# Mergen_Telemetri_Ate_leme.net
KiCad netlist of a schematic drawn in EAGLE
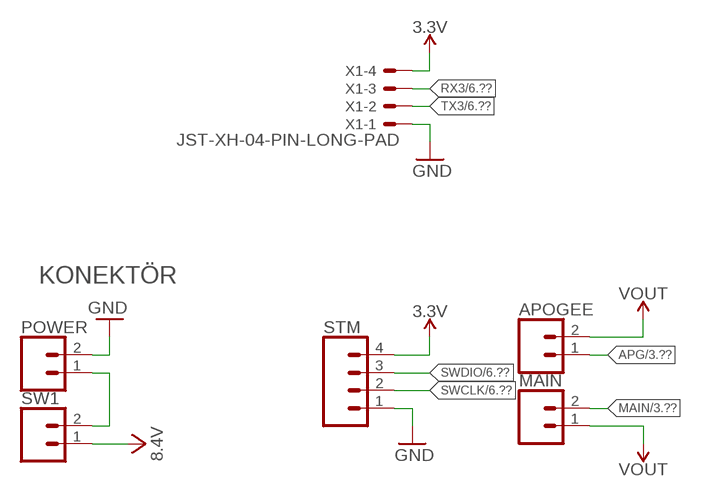
[diagram p0: schematic, sheet 1]
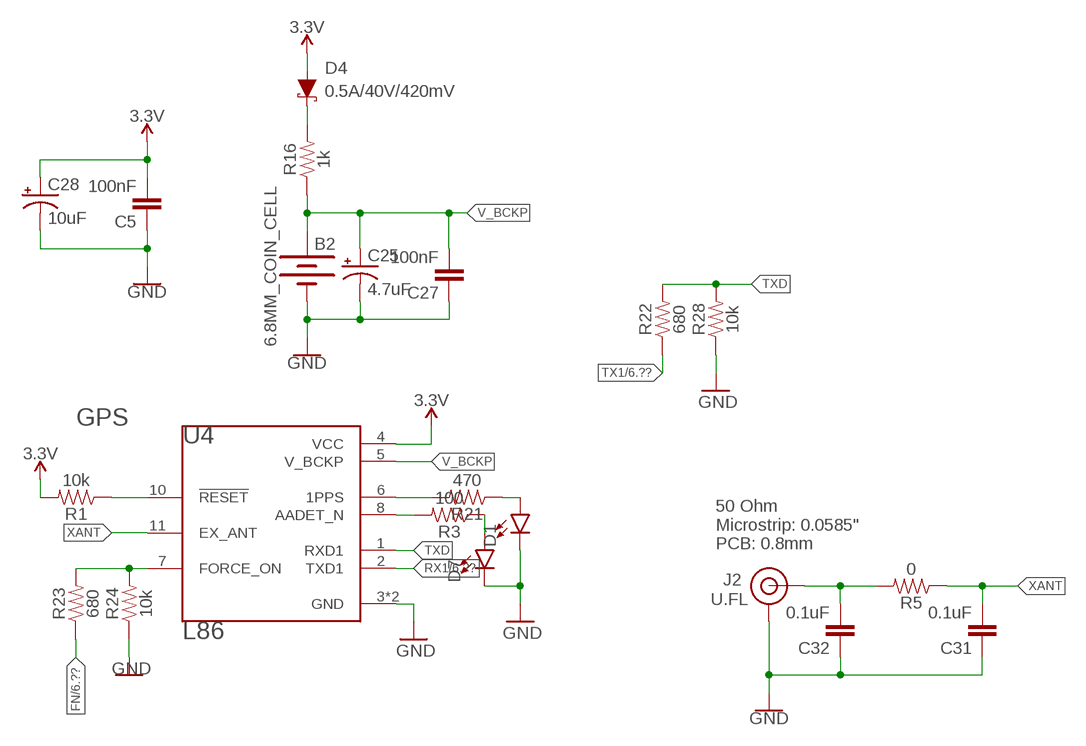
[diagram p1: schematic, sheet 2]
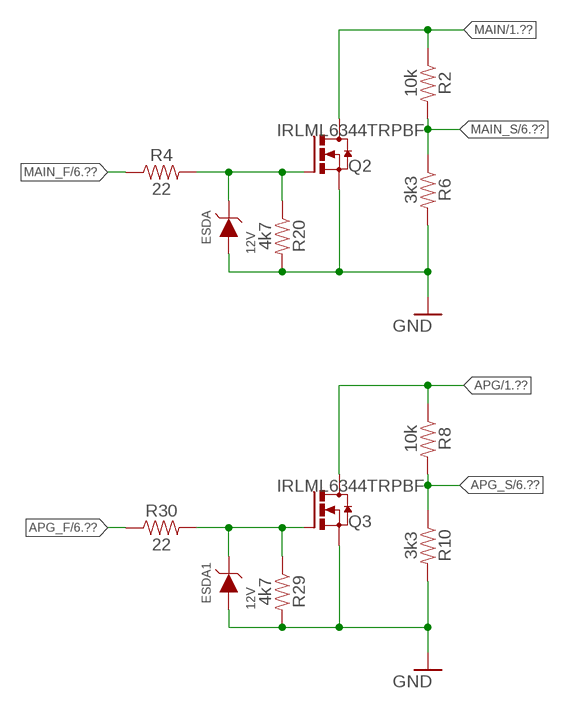
[diagram p2: schematic, sheet 3]
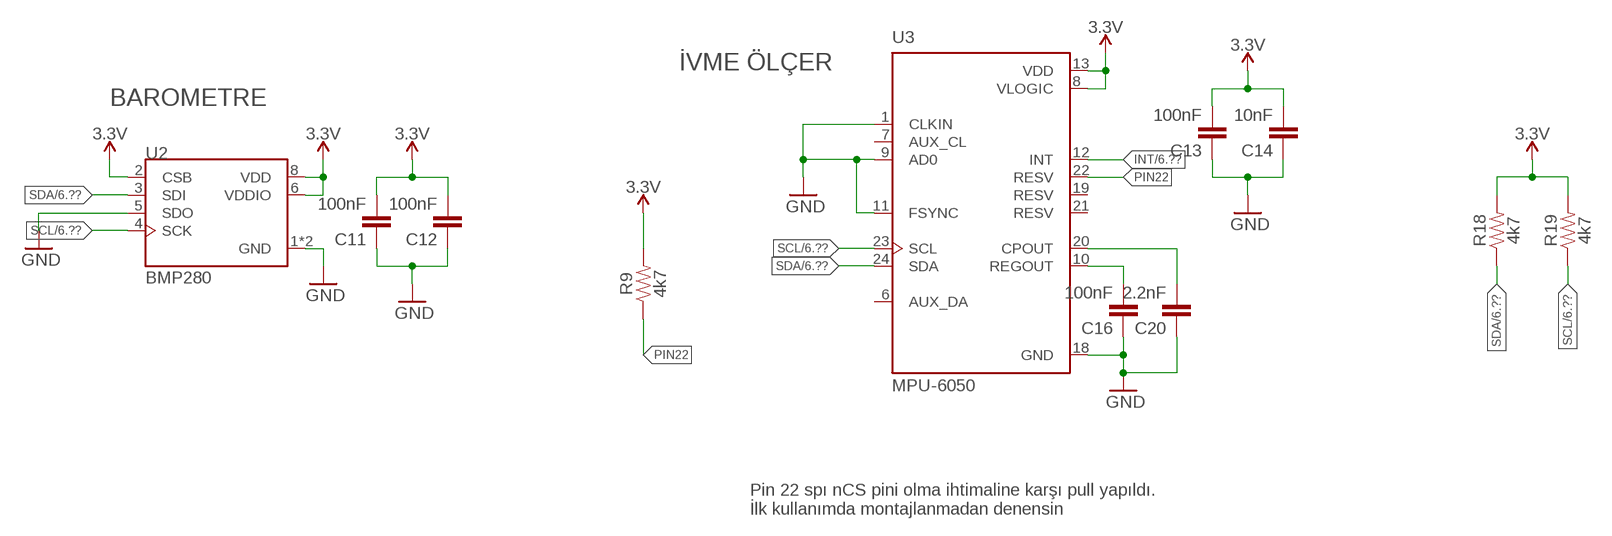
[diagram p3: schematic, sheet 4]
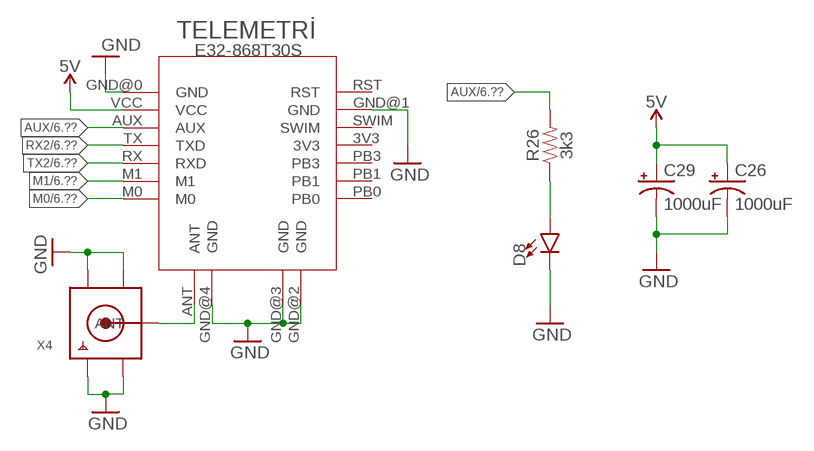
[diagram p4: schematic, sheet 5]
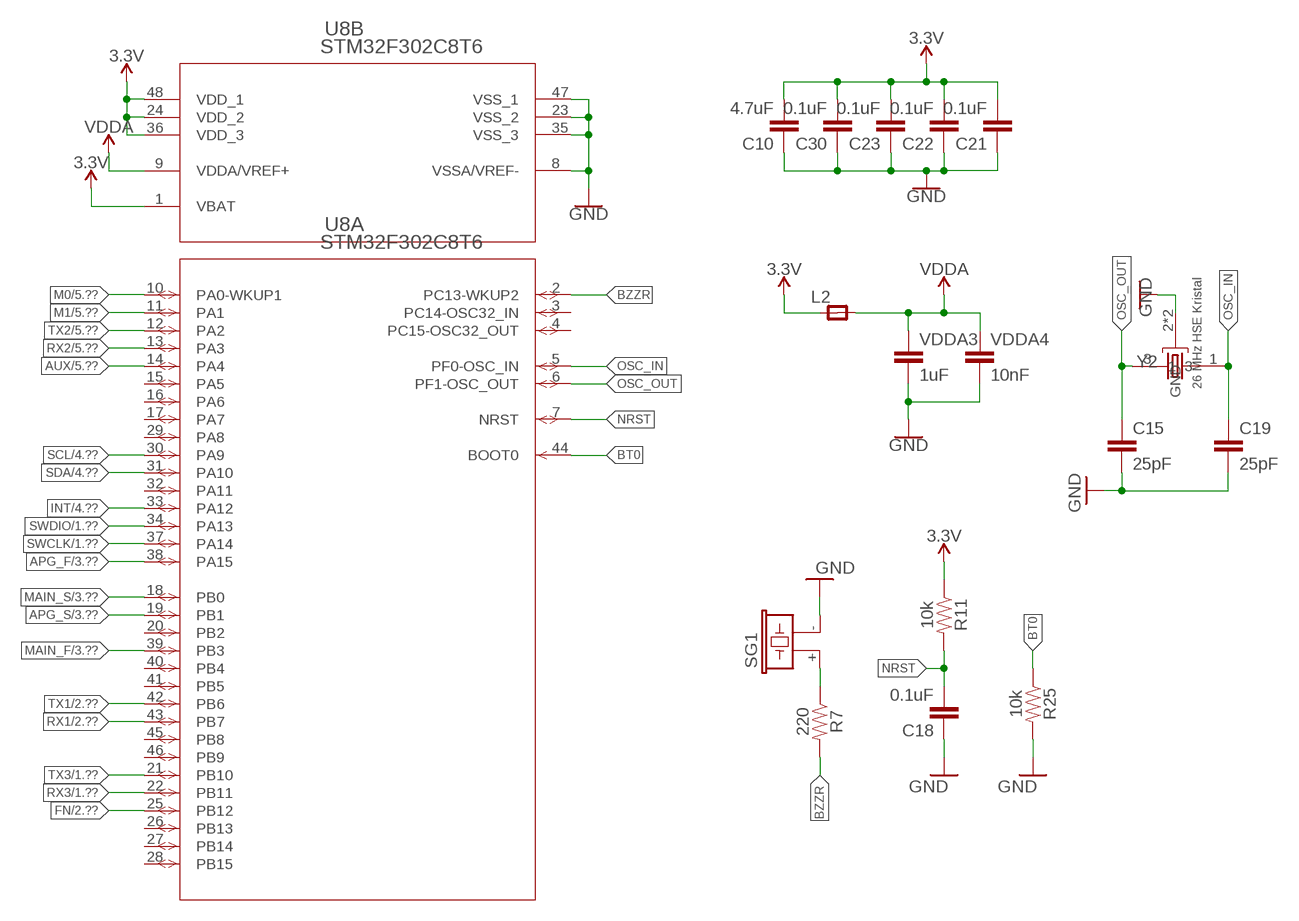
[diagram p5: schematic, sheet 6]
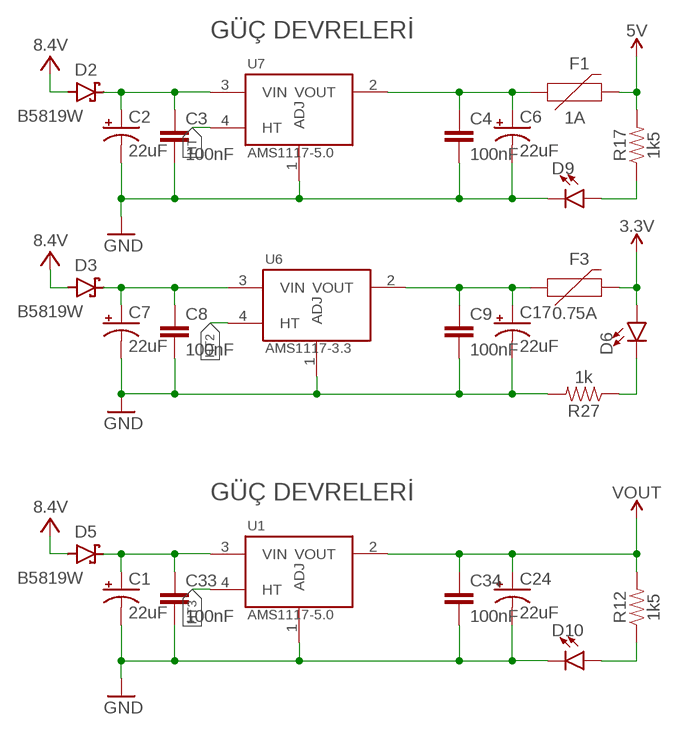
[diagram p6: schematic, sheet 7]

(export (version "E")
  (design (tool "Eeschema 10.0.6"))
  (components
    (comp (ref "ESDA")
      (value "12V")
      (footprint "eagle-import:WE-TVSP_DO-214AC_UNIDIRECTIONAL")
      (libsource (lib "eagle-import") (part "WE-TVSP_DO-214AC_400W_UNI_824500102"))
    )
    (comp (ref "ESDA1")
      (value "12V")
      (footprint "eagle-import:WE-TVSP_DO-214AC_UNIDIRECTIONAL")
      (libsource (lib "eagle-import") (part "WE-TVSP_DO-214AC_400W_UNI_824500102"))
    )
    (comp (ref "Q2")
      (value "IRLML6344TRPBF")
      (footprint "eagle-import:SOT23")
      (fields (field (name "MF") "Infineon"))
      (libsource (lib "eagle-import") (part "IRLML6344TRPBF"))
    )
    (comp (ref "Q3")
      (value "IRLML6344TRPBF")
      (footprint "eagle-import:SOT23")
      (fields (field (name "MF") "Infineon"))
      (libsource (lib "eagle-import") (part "IRLML6344TRPBF"))
    )
    (comp (ref "R2")
      (value "10k")
      (footprint "eagle-import:0603")
      (libsource (lib "eagle-import") (part "SparkFun-Resistors_532_1KOHM-0603-1/10W-1%"))
    )
    (comp (ref "R4")
      (value "22")
      (footprint "eagle-import:0603")
      (libsource (lib "eagle-import") (part "SparkFun-Resistors_532_1KOHM-0603-1/10W-1%"))
    )
    (comp (ref "R6")
      (value "3k3")
      (footprint "eagle-import:0603")
      (libsource (lib "eagle-import") (part "SparkFun-Resistors_532_1KOHM-0603-1/10W-1%"))
    )
    (comp (ref "R8")
      (value "10k")
      (footprint "eagle-import:0603")
      (libsource (lib "eagle-import") (part "SparkFun-Resistors_532_1KOHM-0603-1/10W-1%"))
    )
    (comp (ref "R10")
      (value "3k3")
      (footprint "eagle-import:0603")
      (libsource (lib "eagle-import") (part "SparkFun-Resistors_532_1KOHM-0603-1/10W-1%"))
    )
    (comp (ref "R20")
      (value "4k7")
      (footprint "eagle-import:0603")
      (libsource (lib "eagle-import") (part "SparkFun-Resistors_532_1KOHM-0603-1/10W-1%"))
    )
    (comp (ref "R29")
      (value "4k7")
      (footprint "eagle-import:0603")
      (libsource (lib "eagle-import") (part "SparkFun-Resistors_532_1KOHM-0603-1/10W-1%"))
    )
    (comp (ref "R30")
      (value "22")
      (footprint "eagle-import:0603")
      (libsource (lib "eagle-import") (part "SparkFun-Resistors_532_1KOHM-0603-1/10W-1%"))
    )
    (comp (ref "C10")
      (value "4.7uF")
      (footprint "eagle-import:0603")
      (libsource (lib "eagle-import") (part "1.0UF-0603-16V-10%"))
    )
    (comp (ref "C15")
      (value "25pF")
      (footprint "eagle-import:0603")
      (libsource (lib "eagle-import") (part "1.0UF-0603-16V-10%"))
    )
    (comp (ref "C18")
      (value "0.1uF")
      (footprint "eagle-import:0603")
      (libsource (lib "eagle-import") (part "1.0UF-0603-16V-10%"))
    )
    (comp (ref "C19")
      (value "25pF")
      (footprint "eagle-import:0603")
      (libsource (lib "eagle-import") (part "1.0UF-0603-16V-10%"))
    )
    (comp (ref "C21")
      (value "0.1uF")
      (footprint "eagle-import:0603")
      (libsource (lib "eagle-import") (part "1.0UF-0603-16V-10%"))
    )
    (comp (ref "C22")
      (value "0.1uF")
      (footprint "eagle-import:0603")
      (libsource (lib "eagle-import") (part "1.0UF-0603-16V-10%"))
    )
    (comp (ref "C23")
      (value "0.1uF")
      (footprint "eagle-import:0603")
      (libsource (lib "eagle-import") (part "1.0UF-0603-16V-10%"))
    )
    (comp (ref "C30")
      (value "0.1uF")
      (footprint "eagle-import:0603")
      (libsource (lib "eagle-import") (part "1.0UF-0603-16V-10%"))
    )
    (comp (ref "L2")
      (value "RC-MASTER-SMD_FB_0805MP")
      (footprint "eagle-import:RC-MASTER-SMD_L0805MP")
      (libsource (lib "eagle-import") (part "RC-MASTER-SMD_FB_0805MP"))
    )
    (comp (ref "R7")
      (value "220")
      (footprint "eagle-import:0603")
      (libsource (lib "eagle-import") (part "SparkFun-Resistors_532_1KOHM-0603-1/10W-1%"))
    )
    (comp (ref "R11")
      (value "10k")
      (footprint "eagle-import:0603")
      (libsource (lib "eagle-import") (part "SparkFun-Resistors_532_1KOHM-0603-1/10W-1%"))
    )
    (comp (ref "R25")
      (value "10k")
      (footprint "eagle-import:0603")
      (libsource (lib "eagle-import") (part "SparkFun-Resistors_532_1KOHM-0603-1/10W-1%"))
    )
    (comp (ref "SG1")
      (value "F/CM12P")
      (footprint "eagle-import:F_CM12P")
      (libsource (lib "eagle-import") (part "F/CM12P"))
    )
    (comp (ref "U8")
      (value "STM32F302C8T6")
      (footprint "eagle-import:LQFP48-7X7MM")
      (fields (field (name "COPYRIGHT") "Copyright (C) 2018 Accelerated Designs. All rights reserved"))
      (libsource (lib "eagle-import") (part "STM32F302C8T6"))
    )
    (comp (ref "VDDA3")
      (value "1uF")
      (footprint "eagle-import:0603")
      (libsource (lib "eagle-import") (part "0.1UF-0603-25V-(+80/-20%)"))
    )
    (comp (ref "VDDA4")
      (value "10nF")
      (footprint "eagle-import:0603")
      (libsource (lib "eagle-import") (part "0.1UF-0603-25V-(+80/-20%)"))
    )
    (comp (ref "Y2")
      (value "ABM3B-26.000MHZ-10-1-U-T")
      (footprint "eagle-import:OSCCC500X320X110-4N")
      (fields (field (name "MF") "Abracon"))
      (libsource (lib "eagle-import") (part "ABM3B-26.000MHZ-10-1-U-T"))
    )
    (comp (ref "C1")
      (value "22uF")
      (footprint "eagle-import:EIA3528")
      (libsource (lib "eagle-import") (part "47UF-POLAR-EIA3528-10V-10%"))
    )
    (comp (ref "C2")
      (value "22uF")
      (footprint "eagle-import:EIA3528")
      (libsource (lib "eagle-import") (part "47UF-POLAR-EIA3528-10V-10%"))
    )
    (comp (ref "C3")
      (value "100nF")
      (footprint "eagle-import:0603")
      (libsource (lib "eagle-import") (part "1.0UF-0603-16V-10%"))
    )
    (comp (ref "C4")
      (value "100nF")
      (footprint "eagle-import:0603")
      (libsource (lib "eagle-import") (part "1.0UF-0603-16V-10%"))
    )
    (comp (ref "C6")
      (value "22uF")
      (footprint "eagle-import:EIA3528")
      (libsource (lib "eagle-import") (part "47UF-POLAR-EIA3528-10V-10%"))
    )
    (comp (ref "C7")
      (value "22uF")
      (footprint "eagle-import:EIA3528")
      (libsource (lib "eagle-import") (part "47UF-POLAR-EIA3528-10V-10%"))
    )
    (comp (ref "C8")
      (value "100nF")
      (footprint "eagle-import:0603")
      (libsource (lib "eagle-import") (part "1.0UF-0603-16V-10%"))
    )
    (comp (ref "C9")
      (value "100nF")
      (footprint "eagle-import:0603")
      (libsource (lib "eagle-import") (part "1.0UF-0603-16V-10%"))
    )
    (comp (ref "C17")
      (value "22uF")
      (footprint "eagle-import:EIA3528")
      (libsource (lib "eagle-import") (part "47UF-POLAR-EIA3528-10V-10%"))
    )
    (comp (ref "C24")
      (value "22uF")
      (footprint "eagle-import:EIA3528")
      (libsource (lib "eagle-import") (part "47UF-POLAR-EIA3528-10V-10%"))
    )
    (comp (ref "C33")
      (value "100nF")
      (footprint "eagle-import:0603")
      (libsource (lib "eagle-import") (part "1.0UF-0603-16V-10%"))
    )
    (comp (ref "C34")
      (value "100nF")
      (footprint "eagle-import:0603")
      (libsource (lib "eagle-import") (part "1.0UF-0603-16V-10%"))
    )
    (comp (ref "D2")
      (value "B5819W")
      (footprint "eagle-import:SODFL3718X115")
      (fields (field (name "MANUFACTURER") "ON Semiconductor") (field (name "MPN") "MBR0520LT1G"))
      (libsource (lib "eagle-import") (part "SCHOTTKY_DO-219MBR0520LT1G"))
    )
    (comp (ref "D3")
      (value "B5819W")
      (footprint "eagle-import:SODFL3718X115")
      (fields (field (name "MANUFACTURER") "ON Semiconductor") (field (name "MPN") "MBR0520LT1G"))
      (libsource (lib "eagle-import") (part "SCHOTTKY_DO-219MBR0520LT1G"))
    )
    (comp (ref "D5")
      (value "B5819W")
      (footprint "eagle-import:SODFL3718X115")
      (fields (field (name "MANUFACTURER") "ON Semiconductor") (field (name "MPN") "MBR0520LT1G"))
      (libsource (lib "eagle-import") (part "SCHOTTKY_DO-219MBR0520LT1G"))
    )
    (comp (ref "D6")
      (value "LED0603")
      (footprint "eagle-import:LED-0603")
      (libsource (lib "eagle-import") (part "LED0603"))
    )
    (comp (ref "D9")
      (value "LED0603")
      (footprint "eagle-import:LED-0603")
      (libsource (lib "eagle-import") (part "LED0603"))
    )
    (comp (ref "D10")
      (value "LED0603")
      (footprint "eagle-import:LED-0603")
      (libsource (lib "eagle-import") (part "LED0603"))
    )
    (comp (ref "F1")
      (value "1A")
      (footprint "eagle-import:1206")
      (libsource (lib "eagle-import") (part "PPTC_HALF-AMP"))
    )
    (comp (ref "F3")
      (value "0.75A")
      (footprint "eagle-import:1206")
      (libsource (lib "eagle-import") (part "PPTC_HALF-AMP"))
    )
    (comp (ref "R12")
      (value "1k5")
      (footprint "eagle-import:0603")
      (libsource (lib "eagle-import") (part "SparkFun-Resistors_532_1KOHM-0603-1/10W-1%"))
    )
    (comp (ref "R17")
      (value "1k5")
      (footprint "eagle-import:0603")
      (libsource (lib "eagle-import") (part "SparkFun-Resistors_532_1KOHM-0603-1/10W-1%"))
    )
    (comp (ref "R27")
      (value "1k")
      (footprint "eagle-import:0603")
      (libsource (lib "eagle-import") (part "SparkFun-Resistors_532_1KOHM-0603-1/10W-1%"))
    )
    (comp (ref "U1")
      (value "AMS1117-5.0")
      (footprint "eagle-import:SOT229P700X180-4N")
      (fields (field (name "MF") "Advanced Monolithic Systems") (field (name "MP") "AMS1117-3.3"))
      (libsource (lib "eagle-import") (part "AMS1117-3.3"))
    )
    (comp (ref "U6")
      (value "AMS1117-3.3")
      (footprint "eagle-import:SOT229P700X180-4N")
      (fields (field (name "MF") "Advanced Monolithic Systems"))
      (libsource (lib "eagle-import") (part "AMS1117-3.3"))
    )
    (comp (ref "U7")
      (value "AMS1117-5.0")
      (footprint "eagle-import:SOT229P700X180-4N")
      (fields (field (name "MF") "Advanced Monolithic Systems") (field (name "MP") "AMS1117-3.3"))
      (libsource (lib "eagle-import") (part "AMS1117-3.3"))
    )
    (comp (ref "C26")
      (value "1000uF")
      (footprint "eagle-import:150CLZ-1010")
      (libsource (lib "eagle-import") (part "CPOL-US150CLZ-1010"))
    )
    (comp (ref "C29")
      (value "1000uF")
      (footprint "eagle-import:150CLZ-1010")
      (libsource (lib "eagle-import") (part "CPOL-US150CLZ-1010"))
    )
    (comp (ref "D8")
      (value "LED0603")
      (footprint "eagle-import:LED-0603")
      (libsource (lib "eagle-import") (part "LED0603"))
    )
    (comp (ref "R26")
      (value "3k3")
      (footprint "eagle-import:0603")
      (libsource (lib "eagle-import") (part "SparkFun-Resistors_532_1KOHM-0603-1/10W-1%"))
    )
    (comp (ref "U5")
      (value "E32-868T30S")
      (footprint "eagle-import:E32-868T30S")
      (libsource (lib "eagle-import") (part "E32-868T30S"))
    )
    (comp (ref "X4")
      (value "SMACONNECTOR")
      (footprint "eagle-import:SMA90_DIP")
      (libsource (lib "eagle-import") (part "SMACONNECTOR"))
    )
    (comp (ref "C11")
      (value "100nF")
      (footprint "eagle-import:0603")
      (libsource (lib "eagle-import") (part "1.0UF-0603-16V-10%"))
    )
    (comp (ref "C12")
      (value "100nF")
      (footprint "eagle-import:0603")
      (libsource (lib "eagle-import") (part "1.0UF-0603-16V-10%"))
    )
    (comp (ref "C13")
      (value "100nF")
      (footprint "eagle-import:0603")
      (libsource (lib "eagle-import") (part "1.0UF-0603-16V-10%"))
    )
    (comp (ref "C14")
      (value "10nF")
      (footprint "eagle-import:0603")
      (libsource (lib "eagle-import") (part "1.0UF-0603-16V-10%"))
    )
    (comp (ref "C16")
      (value "100nF")
      (footprint "eagle-import:0603")
      (libsource (lib "eagle-import") (part "1.0UF-0603-16V-10%"))
    )
    (comp (ref "C20")
      (value "2.2nF")
      (footprint "eagle-import:0603")
      (libsource (lib "eagle-import") (part "1.0UF-0603-16V-10%"))
    )
    (comp (ref "R9")
      (value "4k7")
      (footprint "eagle-import:0603")
      (libsource (lib "eagle-import") (part "SparkFun-Resistors_532_1KOHM-0603-1/10W-1%"))
    )
    (comp (ref "R18")
      (value "4k7")
      (footprint "eagle-import:0603")
      (libsource (lib "eagle-import") (part "SparkFun-Resistors_532_1KOHM-0603-1/10W-1%"))
    )
    (comp (ref "R19")
      (value "4k7")
      (footprint "eagle-import:0603")
      (libsource (lib "eagle-import") (part "SparkFun-Resistors_532_1KOHM-0603-1/10W-1%"))
    )
    (comp (ref "U2")
      (value "BMP280")
      (footprint "eagle-import:XDCR_BMP280")
      (fields (field (name "MF") "Bosch"))
      (libsource (lib "eagle-import") (part "BMP280"))
    )
    (comp (ref "U3")
      (value "MPU-6050")
      (footprint "eagle-import:QFN50P400X400X95-24N")
      (fields (field (name "MF") "TDK InvenSense"))
      (libsource (lib "eagle-import") (part "MPU-6050"))
    )
    (comp (ref "APOGEE")
      (value "CONN_023.5MM-NO_SILK")
      (footprint "eagle-import:SCREWTERMINAL-3.5MM-2-NS")
      (libsource (lib "eagle-import") (part "CONN_023.5MM-NO_SILK"))
    )
    (comp (ref "MAIN")
      (value "CONN_023.5MM-NO_SILK")
      (footprint "eagle-import:SCREWTERMINAL-3.5MM-2-NS")
      (libsource (lib "eagle-import") (part "CONN_023.5MM-NO_SILK"))
    )
    (comp (ref "POWER")
      (value "CONN_023.5MM-NO_SILK")
      (footprint "eagle-import:SCREWTERMINAL-3.5MM-2-NS")
      (libsource (lib "eagle-import") (part "CONN_023.5MM-NO_SILK"))
    )
    (comp (ref "STM")
      (value "CONN_04")
      (footprint "eagle-import:1X04")
      (libsource (lib "eagle-import") (part "CONN_04"))
    )
    (comp (ref "SW1")
      (value "CONN_023.5MM-NO_SILK")
      (footprint "eagle-import:SCREWTERMINAL-3.5MM-2-NS")
      (libsource (lib "eagle-import") (part "CONN_023.5MM-NO_SILK"))
    )
    (comp (ref "X1")
      (value "JST-XH-04-PIN-LONG-PAD")
      (footprint "eagle-import:JST-XH-04-PACKAGE-LONG-PAD")
      (libsource (lib "eagle-import") (part "JST-XH-04-PIN-LONG-PAD"))
    )
    (comp (ref "B2")
      (value "6.8MM_COIN_CELL")
      (footprint "eagle-import:BATTCON-6.8MM")
      (libsource (lib "eagle-import") (part "BATTERY-6.8MM_SMD"))
    )
    (comp (ref "C5")
      (value "100nF")
      (footprint "eagle-import:0603")
      (libsource (lib "eagle-import") (part "1.0UF-0603-16V-10%"))
    )
    (comp (ref "C25")
      (value "4.7uF")
      (footprint "eagle-import:EIA3216")
      (libsource (lib "eagle-import") (part "10UF-POLAR-EIA3216-16V-10%(TANT)"))
    )
    (comp (ref "C27")
      (value "100nF")
      (footprint "eagle-import:0603")
      (libsource (lib "eagle-import") (part "1.0UF-0603-16V-10%"))
    )
    (comp (ref "C28")
      (value "10uF")
      (footprint "eagle-import:EIA3216")
      (libsource (lib "eagle-import") (part "10UF-POLAR-EIA3216-16V-10%(TANT)"))
    )
    (comp (ref "C31")
      (value "0.1uF")
      (footprint "eagle-import:0603")
      (libsource (lib "eagle-import") (part "1.0UF-0603-16V-10%"))
    )
    (comp (ref "C32")
      (value "0.1uF")
      (footprint "eagle-import:0603")
      (libsource (lib "eagle-import") (part "1.0UF-0603-16V-10%"))
    )
    (comp (ref "D1")
      (value "LED0603")
      (footprint "eagle-import:LED-0603")
      (libsource (lib "eagle-import") (part "LED0603"))
    )
    (comp (ref "D4")
      (value "0.5A/40V/420mV")
      (footprint "eagle-import:SOD-323")
      (libsource (lib "eagle-import") (part "DIODE-SCHOTTKY-PMEG4005EJ"))
    )
    (comp (ref "D7")
      (value "LED0603")
      (footprint "eagle-import:LED-0603")
      (libsource (lib "eagle-import") (part "LED0603"))
    )
    (comp (ref "J2")
      (value "U.FL")
      (footprint "eagle-import:U.FL")
      (libsource (lib "eagle-import") (part "U.FL2PIN"))
    )
    (comp (ref "R1")
      (value "10k")
      (footprint "eagle-import:0603")
      (libsource (lib "eagle-import") (part "SparkFun-Resistors_532_1KOHM-0603-1/10W-1%"))
    )
    (comp (ref "R3")
      (value "100")
      (footprint "eagle-import:0603")
      (libsource (lib "eagle-import") (part "SparkFun-Resistors_532_1KOHM-0603-1/10W-1%"))
    )
    (comp (ref "R5")
      (value "0")
      (footprint "eagle-import:0603")
      (libsource (lib "eagle-import") (part "SparkFun-Resistors_532_1KOHM-0603-1/10W-1%"))
    )
    (comp (ref "R16")
      (value "1k")
      (footprint "eagle-import:0603")
      (libsource (lib "eagle-import") (part "1KOHM-0603-1/10W-1%"))
    )
    (comp (ref "R21")
      (value "470")
      (footprint "eagle-import:0603")
      (libsource (lib "eagle-import") (part "SparkFun-Resistors_532_1KOHM-0603-1/10W-1%"))
    )
    (comp (ref "R22")
      (value "680")
      (footprint "eagle-import:0603")
      (libsource (lib "eagle-import") (part "SparkFun-Resistors_532_1KOHM-0603-1/10W-1%"))
    )
    (comp (ref "R23")
      (value "680")
      (footprint "eagle-import:0603")
      (libsource (lib "eagle-import") (part "SparkFun-Resistors_532_1KOHM-0603-1/10W-1%"))
    )
    (comp (ref "R24")
      (value "10k")
      (footprint "eagle-import:0603")
      (libsource (lib "eagle-import") (part "SparkFun-Resistors_532_1KOHM-0603-1/10W-1%"))
    )
    (comp (ref "R28")
      (value "10k")
      (footprint "eagle-import:0603")
      (libsource (lib "eagle-import") (part "SparkFun-Resistors_532_1KOHM-0603-1/10W-1%"))
    )
    (comp (ref "U4")
      (value "L86")
      (footprint "eagle-import:XCVR_L86")
      (fields (field (name "MF") "Quectel"))
      (libsource (lib "eagle-import") (part "L86"))
    )
  )
  (nets
    (net (code "1") (name "3.3V") (class "Default")
      (node (ref "C10") (pin "2") (pinfunction "2_2") (pintype "passive"))
      (node (ref "C11") (pin "2") (pinfunction "2_2") (pintype "passive"))
      (node (ref "C12") (pin "2") (pinfunction "2_2") (pintype "passive"))
      (node (ref "C13") (pin "2") (pinfunction "2_2") (pintype "passive"))
      (node (ref "C14") (pin "2") (pinfunction "2_2") (pintype "passive"))
      (node (ref "C21") (pin "2") (pinfunction "2_2") (pintype "passive"))
      (node (ref "C22") (pin "2") (pinfunction "2_2") (pintype "passive"))
      (node (ref "C23") (pin "2") (pinfunction "2_2") (pintype "passive"))
      (node (ref "C28") (pin "+") (pinfunction "+_+") (pintype "passive"))
      (node (ref "C30") (pin "2") (pinfunction "2_2") (pintype "passive"))
      (node (ref "C5") (pin "2") (pinfunction "2_2") (pintype "passive"))
      (node (ref "D4") (pin "A") (pinfunction "A_A") (pintype "passive"))
      (node (ref "D6") (pin "A") (pinfunction "A_A") (pintype "passive"))
      (node (ref "F3") (pin "2") (pinfunction "2_2") (pintype "bidirectional"))
      (node (ref "L2") (pin "1") (pinfunction "1_1") (pintype "passive"))
      (node (ref "R1") (pin "2") (pinfunction "2_2") (pintype "passive"))
      (node (ref "R11") (pin "1") (pinfunction "1_1") (pintype "passive"))
      (node (ref "R18") (pin "2") (pinfunction "2_2") (pintype "passive"))
      (node (ref "R19") (pin "2") (pinfunction "2_2") (pintype "passive"))
      (node (ref "R9") (pin "2") (pinfunction "2_2") (pintype "passive"))
      (node (ref "STM") (pin "4") (pinfunction "4_4") (pintype "passive"))
      (node (ref "U2") (pin "2") (pinfunction "CSB_2") (pintype "input"))
      (node (ref "U2") (pin "6") (pinfunction "VDDIO_6") (pintype "power_in"))
      (node (ref "U2") (pin "8") (pinfunction "VDD_8") (pintype "power_in"))
      (node (ref "U3") (pin "13") (pinfunction "VDD_13") (pintype "power_in"))
      (node (ref "U3") (pin "8") (pinfunction "VLOGIC_8") (pintype "power_in"))
      (node (ref "U4") (pin "4") (pinfunction "VCC_4") (pintype "power_in"))
      (node (ref "U8") (pin "1") (pinfunction "VBAT_1") (pintype "power_in"))
      (node (ref "U8") (pin "24") (pinfunction "VDD_2_24") (pintype "power_in"))
      (node (ref "U8") (pin "36") (pinfunction "VDD_3_36") (pintype "power_in"))
      (node (ref "U8") (pin "48") (pinfunction "VDD_1_48") (pintype "power_in"))
      (node (ref "X1") (pin "4") (pinfunction "S_4") (pintype "passive"))
    )
    (net (code "2") (name "5V") (class "Default")
      (node (ref "C26") (pin "+") (pinfunction "+_+") (pintype "passive"))
      (node (ref "C29") (pin "+") (pinfunction "+_+") (pintype "passive"))
      (node (ref "F1") (pin "2") (pinfunction "2_2") (pintype "bidirectional"))
      (node (ref "R17") (pin "2") (pinfunction "2_2") (pintype "passive"))
      (node (ref "U5") (pin "VCC") (pinfunction "VCC_VCC") (pintype "bidirectional"))
    )
    (net (code "3") (name "APG") (class "Default")
      (node (ref "APOGEE") (pin "1") (pinfunction "1_1") (pintype "passive"))
      (node (ref "Q3") (pin "3") (pinfunction "D_3") (pintype "passive"))
      (node (ref "R8") (pin "1") (pinfunction "1_1") (pintype "passive"))
    )
    (net (code "4") (name "APG_F") (class "Default")
      (node (ref "R30") (pin "1") (pinfunction "1_1") (pintype "passive"))
      (node (ref "U8") (pin "38") (pinfunction "PA15_38") (pintype "bidirectional"))
    )
    (net (code "5") (name "APG_S") (class "Default")
      (node (ref "R10") (pin "1") (pinfunction "1_1") (pintype "passive"))
      (node (ref "R8") (pin "2") (pinfunction "2_2") (pintype "passive"))
      (node (ref "U8") (pin "19") (pinfunction "PB1_19") (pintype "bidirectional"))
    )
    (net (code "6") (name "AUX") (class "Default")
      (node (ref "R26") (pin "2") (pinfunction "2_2") (pintype "passive"))
      (node (ref "U5") (pin "AUX") (pinfunction "AUX_AUX") (pintype "bidirectional"))
      (node (ref "U8") (pin "14") (pinfunction "PA4_14") (pintype "bidirectional"))
    )
    (net (code "7") (name "BT0") (class "Default")
      (node (ref "R25") (pin "1") (pinfunction "1_1") (pintype "passive"))
      (node (ref "U8") (pin "44") (pinfunction "BOOT0_44") (pintype "input"))
    )
    (net (code "8") (name "BZZR") (class "Default")
      (node (ref "R7") (pin "2") (pinfunction "2_2") (pintype "passive"))
      (node (ref "U8") (pin "2") (pinfunction "PC13-WKUP2_2") (pintype "bidirectional"))
    )
    (net (code "9") (name "FN") (class "Default")
      (node (ref "R23") (pin "1") (pinfunction "1_1") (pintype "passive"))
      (node (ref "U8") (pin "25") (pinfunction "PB12_25") (pintype "bidirectional"))
    )
    (net (code "10") (name "GND") (class "Default")
      (node (ref "B2") (pin "-") (pinfunction "-_-") (pintype "power_in"))
      (node (ref "C1") (pin "C") (pinfunction "-_C") (pintype "passive"))
      (node (ref "C10") (pin "1") (pinfunction "1_1") (pintype "passive"))
      (node (ref "C11") (pin "1") (pinfunction "1_1") (pintype "passive"))
      (node (ref "C12") (pin "1") (pinfunction "1_1") (pintype "passive"))
      (node (ref "C13") (pin "1") (pinfunction "1_1") (pintype "passive"))
      (node (ref "C14") (pin "1") (pinfunction "1_1") (pintype "passive"))
      (node (ref "C15") (pin "2") (pinfunction "2_2") (pintype "passive"))
      (node (ref "C16") (pin "1") (pinfunction "1_1") (pintype "passive"))
      (node (ref "C17") (pin "C") (pinfunction "-_C") (pintype "passive"))
      (node (ref "C18") (pin "1") (pinfunction "1_1") (pintype "passive"))
      (node (ref "C19") (pin "2") (pinfunction "2_2") (pintype "passive"))
      (node (ref "C2") (pin "C") (pinfunction "-_C") (pintype "passive"))
      (node (ref "C20") (pin "1") (pinfunction "1_1") (pintype "passive"))
      (node (ref "C21") (pin "1") (pinfunction "1_1") (pintype "passive"))
      (node (ref "C22") (pin "1") (pinfunction "1_1") (pintype "passive"))
      (node (ref "C23") (pin "1") (pinfunction "1_1") (pintype "passive"))
      (node (ref "C24") (pin "C") (pinfunction "-_C") (pintype "passive"))
      (node (ref "C25") (pin "-") (pinfunction "-_-") (pintype "passive"))
      (node (ref "C26") (pin "-") (pinfunction "-_-") (pintype "passive"))
      (node (ref "C27") (pin "1") (pinfunction "1_1") (pintype "passive"))
      (node (ref "C28") (pin "-") (pinfunction "-_-") (pintype "passive"))
      (node (ref "C29") (pin "-") (pinfunction "-_-") (pintype "passive"))
      (node (ref "C3") (pin "2") (pinfunction "2_2") (pintype "passive"))
      (node (ref "C30") (pin "1") (pinfunction "1_1") (pintype "passive"))
      (node (ref "C31") (pin "1") (pinfunction "1_1") (pintype "passive"))
      (node (ref "C32") (pin "1") (pinfunction "1_1") (pintype "passive"))
      (node (ref "C33") (pin "2") (pinfunction "2_2") (pintype "passive"))
      (node (ref "C34") (pin "2") (pinfunction "2_2") (pintype "passive"))
      (node (ref "C4") (pin "2") (pinfunction "2_2") (pintype "passive"))
      (node (ref "C5") (pin "1") (pinfunction "1_1") (pintype "passive"))
      (node (ref "C6") (pin "C") (pinfunction "-_C") (pintype "passive"))
      (node (ref "C7") (pin "C") (pinfunction "-_C") (pintype "passive"))
      (node (ref "C8") (pin "2") (pinfunction "2_2") (pintype "passive"))
      (node (ref "C9") (pin "2") (pinfunction "2_2") (pintype "passive"))
      (node (ref "D1") (pin "C") (pinfunction "C_C") (pintype "passive"))
      (node (ref "D10") (pin "C") (pinfunction "C_C") (pintype "passive"))
      (node (ref "D7") (pin "C") (pinfunction "C_C") (pintype "passive"))
      (node (ref "D8") (pin "C") (pinfunction "C_C") (pintype "passive"))
      (node (ref "D9") (pin "C") (pinfunction "C_C") (pintype "passive"))
      (node (ref "ESDA") (pin "2") (pinfunction "A_2") (pintype "passive"))
      (node (ref "ESDA1") (pin "2") (pinfunction "A_2") (pintype "passive"))
      (node (ref "J2") (pin "1") (pinfunction "GND_1") (pintype "bidirectional"))
      (node (ref "J2") (pin "2") (pinfunction "GND_2") (pintype "bidirectional"))
      (node (ref "POWER") (pin "2") (pinfunction "2_2") (pintype "passive"))
      (node (ref "Q2") (pin "2") (pinfunction "S_2") (pintype "passive"))
      (node (ref "Q3") (pin "2") (pinfunction "S_2") (pintype "passive"))
      (node (ref "R10") (pin "2") (pinfunction "2_2") (pintype "passive"))
      (node (ref "R20") (pin "2") (pinfunction "2_2") (pintype "passive"))
      (node (ref "R24") (pin "1") (pinfunction "1_1") (pintype "passive"))
      (node (ref "R25") (pin "2") (pinfunction "2_2") (pintype "passive"))
      (node (ref "R27") (pin "2") (pinfunction "2_2") (pintype "passive"))
      (node (ref "R28") (pin "1") (pinfunction "1_1") (pintype "passive"))
      (node (ref "R29") (pin "2") (pinfunction "2_2") (pintype "passive"))
      (node (ref "R6") (pin "2") (pinfunction "2_2") (pintype "passive"))
      (node (ref "SG1") (pin "-") (pinfunction "2_-") (pintype "passive"))
      (node (ref "STM") (pin "1") (pinfunction "1_1") (pintype "passive"))
      (node (ref "U1") (pin "1") (pinfunction "ADJ_1") (pintype "power_in"))
      (node (ref "U2") (pin "1") (pinfunction "GND_1") (pintype "power_in"))
      (node (ref "U2") (pin "5") (pinfunction "SDO_5") (pintype "bidirectional"))
      (node (ref "U2") (pin "7") (pinfunction "GND_7") (pintype "power_in"))
      (node (ref "U3") (pin "1") (pinfunction "CLKIN_1") (pintype "input"))
      (node (ref "U3") (pin "11") (pinfunction "FSYNC_11") (pintype "input"))
      (node (ref "U3") (pin "18") (pinfunction "GND_18") (pintype "power_in"))
      (node (ref "U3") (pin "9") (pinfunction "AD0_9") (pintype "input"))
      (node (ref "U4") (pin "12") (pinfunction "GND_12") (pintype "passive"))
      (node (ref "U4") (pin "3") (pinfunction "GND_3") (pintype "passive"))
      (node (ref "U5") (pin "GND@0") (pinfunction "GND_GND@0") (pintype "bidirectional"))
      (node (ref "U5") (pin "GND@1") (pinfunction "GND_GND@1") (pintype "bidirectional"))
      (node (ref "U5") (pin "GND@2") (pinfunction "GND_GND@2") (pintype "bidirectional"))
      (node (ref "U5") (pin "GND@3") (pinfunction "GND_GND@3") (pintype "bidirectional"))
      (node (ref "U5") (pin "GND@4") (pinfunction "GND_GND@4") (pintype "bidirectional"))
      (node (ref "U6") (pin "1") (pinfunction "ADJ_1") (pintype "power_in"))
      (node (ref "U7") (pin "1") (pinfunction "ADJ_1") (pintype "power_in"))
      (node (ref "U8") (pin "23") (pinfunction "VSS_2_23") (pintype "power_in"))
      (node (ref "U8") (pin "35") (pinfunction "VSS_3_35") (pintype "power_in"))
      (node (ref "U8") (pin "47") (pinfunction "VSS_1_47") (pintype "power_in"))
      (node (ref "U8") (pin "8") (pinfunction "VSSA/VREF-_8") (pintype "power_in"))
      (node (ref "VDDA3") (pin "2") (pinfunction "2_2") (pintype "passive"))
      (node (ref "VDDA4") (pin "2") (pinfunction "2_2") (pintype "passive"))
      (node (ref "X1") (pin "1") (pinfunction "S_1") (pintype "passive"))
      (node (ref "X4") (pin "GND1") (pinfunction "GND1_GND1") (pintype "power_in"))
      (node (ref "X4") (pin "GND2") (pinfunction "GND2_GND2") (pintype "power_in"))
      (node (ref "X4") (pin "GND3") (pinfunction "GND3_GND3") (pintype "power_in"))
      (node (ref "X4") (pin "GND4") (pinfunction "GND4_GND4") (pintype "power_in"))
      (node (ref "Y2") (pin "2") (pinfunction "GND_2") (pintype "passive"))
      (node (ref "Y2") (pin "4") (pinfunction "GND_4") (pintype "passive"))
    )
    (net (code "11") (name "HT") (class "Default")
      (node (ref "U7") (pin "4") (pinfunction "HT_4") (pintype "bidirectional"))
    )
    (net (code "12") (name "HT2") (class "Default")
      (node (ref "U6") (pin "4") (pinfunction "HT_4") (pintype "bidirectional"))
    )
    (net (code "13") (name "HT3") (class "Default")
      (node (ref "U1") (pin "4") (pinfunction "HT_4") (pintype "bidirectional"))
    )
    (net (code "14") (name "INT") (class "Default")
      (node (ref "U3") (pin "12") (pinfunction "INT_12") (pintype "output"))
      (node (ref "U8") (pin "33") (pinfunction "PA12_33") (pintype "bidirectional"))
    )
    (net (code "15") (name "M0") (class "Default")
      (node (ref "U5") (pin "M0") (pinfunction "M0_M0") (pintype "bidirectional"))
      (node (ref "U8") (pin "10") (pinfunction "PA0-WKUP1_10") (pintype "bidirectional"))
    )
    (net (code "16") (name "M1") (class "Default")
      (node (ref "U5") (pin "M1") (pinfunction "M1_M1") (pintype "bidirectional"))
      (node (ref "U8") (pin "11") (pinfunction "PA1_11") (pintype "bidirectional"))
    )
    (net (code "17") (name "MAIN") (class "Default")
      (node (ref "MAIN") (pin "2") (pinfunction "2_2") (pintype "passive"))
      (node (ref "Q2") (pin "3") (pinfunction "D_3") (pintype "passive"))
      (node (ref "R2") (pin "1") (pinfunction "1_1") (pintype "passive"))
    )
    (net (code "18") (name "MAIN_F") (class "Default")
      (node (ref "R4") (pin "1") (pinfunction "1_1") (pintype "passive"))
      (node (ref "U8") (pin "39") (pinfunction "PB3_39") (pintype "bidirectional"))
    )
    (net (code "19") (name "MAIN_S") (class "Default")
      (node (ref "R2") (pin "2") (pinfunction "2_2") (pintype "passive"))
      (node (ref "R6") (pin "1") (pinfunction "1_1") (pintype "passive"))
      (node (ref "U8") (pin "18") (pinfunction "PB0_18") (pintype "bidirectional"))
    )
    (net (code "20") (name "NRST") (class "Default")
      (node (ref "C18") (pin "2") (pinfunction "2_2") (pintype "passive"))
      (node (ref "R11") (pin "2") (pinfunction "2_2") (pintype "passive"))
      (node (ref "U8") (pin "7") (pinfunction "NRST_7") (pintype "bidirectional"))
    )
    (net (code "21") (name "Net-(C1-+)") (class "Default")
      (node (ref "C1") (pin "A") (pinfunction "+_A") (pintype "passive"))
      (node (ref "C33") (pin "1") (pinfunction "1_1") (pintype "passive"))
      (node (ref "D5") (pin "1") (pinfunction "C_1") (pintype "passive"))
      (node (ref "U1") (pin "3") (pinfunction "VIN_3") (pintype "input"))
    )
    (net (code "22") (name "Net-(C2-+)") (class "Default")
      (node (ref "C2") (pin "A") (pinfunction "+_A") (pintype "passive"))
      (node (ref "C3") (pin "1") (pinfunction "1_1") (pintype "passive"))
      (node (ref "D2") (pin "1") (pinfunction "C_1") (pintype "passive"))
      (node (ref "U7") (pin "3") (pinfunction "VIN_3") (pintype "input"))
    )
    (net (code "23") (name "Net-(C6-+)") (class "Default")
      (node (ref "C4") (pin "1") (pinfunction "1_1") (pintype "passive"))
      (node (ref "C6") (pin "A") (pinfunction "+_A") (pintype "passive"))
      (node (ref "F1") (pin "1") (pinfunction "1_1") (pintype "bidirectional"))
      (node (ref "U7") (pin "2") (pinfunction "VOUT_2") (pintype "output"))
    )
    (net (code "24") (name "Net-(C7-+)") (class "Default")
      (node (ref "C7") (pin "A") (pinfunction "+_A") (pintype "passive"))
      (node (ref "C8") (pin "1") (pinfunction "1_1") (pintype "passive"))
      (node (ref "D3") (pin "1") (pinfunction "C_1") (pintype "passive"))
      (node (ref "U6") (pin "3") (pinfunction "VIN_3") (pintype "input"))
    )
    (net (code "25") (name "Net-(C17-+)") (class "Default")
      (node (ref "C17") (pin "A") (pinfunction "+_A") (pintype "passive"))
      (node (ref "C9") (pin "1") (pinfunction "1_1") (pintype "passive"))
      (node (ref "F3") (pin "1") (pinfunction "1_1") (pintype "bidirectional"))
      (node (ref "U6") (pin "2") (pinfunction "VOUT_2") (pintype "output"))
    )
    (net (code "26") (name "Net-(D1-PadA)") (class "Default")
      (node (ref "D1") (pin "A") (pinfunction "A_A") (pintype "passive"))
      (node (ref "R21") (pin "1") (pinfunction "1_1") (pintype "passive"))
    )
    (net (code "27") (name "Net-(D4-PadC)") (class "Default")
      (node (ref "D4") (pin "C") (pinfunction "C_C") (pintype "passive"))
      (node (ref "R16") (pin "2") (pinfunction "2_2") (pintype "passive"))
    )
    (net (code "28") (name "Net-(D6-PadC)") (class "Default")
      (node (ref "D6") (pin "C") (pinfunction "C_C") (pintype "passive"))
      (node (ref "R27") (pin "1") (pinfunction "1_1") (pintype "passive"))
    )
    (net (code "29") (name "Net-(D7-PadA)") (class "Default")
      (node (ref "D7") (pin "A") (pinfunction "A_A") (pintype "passive"))
      (node (ref "R3") (pin "1") (pinfunction "1_1") (pintype "passive"))
    )
    (net (code "30") (name "Net-(D8-PadA)") (class "Default")
      (node (ref "D8") (pin "A") (pinfunction "A_A") (pintype "passive"))
      (node (ref "R26") (pin "1") (pinfunction "1_1") (pintype "passive"))
    )
    (net (code "31") (name "Net-(D9-PadA)") (class "Default")
      (node (ref "D9") (pin "A") (pinfunction "A_A") (pintype "passive"))
      (node (ref "R17") (pin "1") (pinfunction "1_1") (pintype "passive"))
    )
    (net (code "32") (name "Net-(D10-PadA)") (class "Default")
      (node (ref "D10") (pin "A") (pinfunction "A_A") (pintype "passive"))
      (node (ref "R12") (pin "1") (pinfunction "1_1") (pintype "passive"))
    )
    (net (code "33") (name "Net-(ESDA-C)") (class "Default")
      (node (ref "ESDA") (pin "1") (pinfunction "C_1") (pintype "passive"))
      (node (ref "Q2") (pin "1") (pinfunction "G_1") (pintype "passive"))
      (node (ref "R20") (pin "1") (pinfunction "1_1") (pintype "passive"))
      (node (ref "R4") (pin "2") (pinfunction "2_2") (pintype "passive"))
    )
    (net (code "34") (name "Net-(ESDA1-C)") (class "Default")
      (node (ref "ESDA1") (pin "1") (pinfunction "C_1") (pintype "passive"))
      (node (ref "Q3") (pin "1") (pinfunction "G_1") (pintype "passive"))
      (node (ref "R29") (pin "1") (pinfunction "1_1") (pintype "passive"))
      (node (ref "R30") (pin "2") (pinfunction "2_2") (pintype "passive"))
    )
    (net (code "35") (name "Net-(J2-SIGNAL)") (class "Default")
      (node (ref "C32") (pin "2") (pinfunction "2_2") (pintype "passive"))
      (node (ref "J2") (pin "FEED") (pinfunction "SIGNAL_FEED") (pintype "bidirectional"))
      (node (ref "R5") (pin "2") (pinfunction "2_2") (pintype "passive"))
    )
    (net (code "36") (name "Net-(POWER-Pad1)") (class "Default")
      (node (ref "POWER") (pin "1") (pinfunction "1_1") (pintype "passive"))
      (node (ref "SW1") (pin "2") (pinfunction "2_2") (pintype "passive"))
    )
    (net (code "37") (name "Net-(SG1-1)") (class "Default")
      (node (ref "R7") (pin "1") (pinfunction "1_1") (pintype "passive"))
      (node (ref "SG1") (pin "+") (pinfunction "1_+") (pintype "passive"))
    )
    (net (code "38") (name "Net-(U3-CPOUT)") (class "Default")
      (node (ref "C20") (pin "2") (pinfunction "2_2") (pintype "passive"))
      (node (ref "U3") (pin "20") (pinfunction "CPOUT_20") (pintype "passive"))
    )
    (net (code "39") (name "Net-(U3-REGOUT)") (class "Default")
      (node (ref "C16") (pin "2") (pinfunction "2_2") (pintype "passive"))
      (node (ref "U3") (pin "10") (pinfunction "REGOUT_10") (pintype "passive"))
    )
    (net (code "40") (name "Net-(U4-1PPS)") (class "Default")
      (node (ref "R21") (pin "2") (pinfunction "2_2") (pintype "passive"))
      (node (ref "U4") (pin "6") (pinfunction "1PPS_6") (pintype "output"))
    )
    (net (code "41") (name "Net-(U4-AADET_N)") (class "Default")
      (node (ref "R3") (pin "2") (pinfunction "2_2") (pintype "passive"))
      (node (ref "U4") (pin "8") (pinfunction "AADET_N_8") (pintype "output"))
    )
    (net (code "42") (name "Net-(U4-FORCE_ON)") (class "Default")
      (node (ref "R23") (pin "2") (pinfunction "2_2") (pintype "passive"))
      (node (ref "R24") (pin "2") (pinfunction "2_2") (pintype "passive"))
      (node (ref "U4") (pin "7") (pinfunction "FORCE_ON_7") (pintype "input"))
    )
    (net (code "43") (name "Net-(U4-~{RESET})") (class "Default")
      (node (ref "R1") (pin "1") (pinfunction "1_1") (pintype "passive"))
      (node (ref "U4") (pin "10") (pinfunction "~{RESET}_10") (pintype "input"))
    )
    (net (code "44") (name "Net-(X4-ANT)") (class "Default")
      (node (ref "U5") (pin "ANT") (pinfunction "ANT_ANT") (pintype "bidirectional"))
      (node (ref "X4") (pin "ANTENNA") (pinfunction "ANT_ANTENNA") (pintype "bidirectional"))
    )
    (net (code "45") (name "OSC_IN") (class "Default")
      (node (ref "C19") (pin "1") (pinfunction "1_1") (pintype "passive"))
      (node (ref "U8") (pin "5") (pinfunction "PF0-OSC_IN_5") (pintype "bidirectional"))
      (node (ref "Y2") (pin "1") (pinfunction "1_1") (pintype "passive"))
    )
    (net (code "46") (name "OSC_OUT") (class "Default")
      (node (ref "C15") (pin "1") (pinfunction "1_1") (pintype "passive"))
      (node (ref "U8") (pin "6") (pinfunction "PF1-OSC_OUT_6") (pintype "bidirectional"))
      (node (ref "Y2") (pin "3") (pinfunction "3_3") (pintype "passive"))
    )
    (net (code "47") (name "PIN22") (class "Default")
      (node (ref "R9") (pin "1") (pinfunction "1_1") (pintype "passive"))
      (node (ref "U3") (pin "22") (pinfunction "RESV_22") (pintype "passive"))
    )
    (net (code "48") (name "RX1") (class "Default")
      (node (ref "U4") (pin "2") (pinfunction "TXD1_2") (pintype "output"))
      (node (ref "U8") (pin "43") (pinfunction "PB7_43") (pintype "bidirectional"))
    )
    (net (code "49") (name "RX2") (class "Default")
      (node (ref "U5") (pin "TX") (pinfunction "TXD_TX") (pintype "bidirectional"))
      (node (ref "U8") (pin "13") (pinfunction "PA3_13") (pintype "bidirectional"))
    )
    (net (code "50") (name "RX3") (class "Default")
      (node (ref "U8") (pin "22") (pinfunction "PB11_22") (pintype "bidirectional"))
      (node (ref "X1") (pin "3") (pinfunction "S_3") (pintype "passive"))
    )
    (net (code "51") (name "SCL") (class "Default")
      (node (ref "R19") (pin "1") (pinfunction "1_1") (pintype "passive"))
      (node (ref "U2") (pin "4") (pinfunction "SCK_4") (pintype "input"))
      (node (ref "U3") (pin "23") (pinfunction "SCL_23") (pintype "input"))
      (node (ref "U8") (pin "30") (pinfunction "PA9_30") (pintype "bidirectional"))
    )
    (net (code "52") (name "SDA") (class "Default")
      (node (ref "R18") (pin "1") (pinfunction "1_1") (pintype "passive"))
      (node (ref "U2") (pin "3") (pinfunction "SDI_3") (pintype "bidirectional"))
      (node (ref "U3") (pin "24") (pinfunction "SDA_24") (pintype "bidirectional"))
      (node (ref "U8") (pin "31") (pinfunction "PA10_31") (pintype "bidirectional"))
    )
    (net (code "53") (name "SWCLK") (class "Default")
      (node (ref "STM") (pin "2") (pinfunction "2_2") (pintype "passive"))
      (node (ref "U8") (pin "37") (pinfunction "PA14_37") (pintype "bidirectional"))
    )
    (net (code "54") (name "SWDIO") (class "Default")
      (node (ref "STM") (pin "3") (pinfunction "3_3") (pintype "passive"))
      (node (ref "U8") (pin "34") (pinfunction "PA13_34") (pintype "bidirectional"))
    )
    (net (code "55") (name "TX1") (class "Default")
      (node (ref "R22") (pin "1") (pinfunction "1_1") (pintype "passive"))
      (node (ref "U8") (pin "42") (pinfunction "PB6_42") (pintype "bidirectional"))
    )
    (net (code "56") (name "TX2") (class "Default")
      (node (ref "U5") (pin "RX") (pinfunction "RXD_RX") (pintype "bidirectional"))
      (node (ref "U8") (pin "12") (pinfunction "PA2_12") (pintype "bidirectional"))
    )
    (net (code "57") (name "TX3") (class "Default")
      (node (ref "U8") (pin "21") (pinfunction "PB10_21") (pintype "bidirectional"))
      (node (ref "X1") (pin "2") (pinfunction "S_2") (pintype "passive"))
    )
    (net (code "58") (name "TXD") (class "Default")
      (node (ref "R22") (pin "2") (pinfunction "2_2") (pintype "passive"))
      (node (ref "R28") (pin "2") (pinfunction "2_2") (pintype "passive"))
      (node (ref "U4") (pin "1") (pinfunction "RXD1_1") (pintype "input"))
    )
    (net (code "59") (name "VCC") (class "Default")
      (node (ref "D2") (pin "2") (pinfunction "A_2") (pintype "passive"))
      (node (ref "D3") (pin "2") (pinfunction "A_2") (pintype "passive"))
      (node (ref "D5") (pin "2") (pinfunction "A_2") (pintype "passive"))
      (node (ref "SW1") (pin "1") (pinfunction "1_1") (pintype "passive"))
    )
    (net (code "60") (name "VDDA") (class "Default")
      (node (ref "L2") (pin "2") (pinfunction "2_2") (pintype "passive"))
      (node (ref "U8") (pin "9") (pinfunction "VDDA/VREF+_9") (pintype "power_in"))
      (node (ref "VDDA3") (pin "1") (pinfunction "1_1") (pintype "passive"))
      (node (ref "VDDA4") (pin "1") (pinfunction "1_1") (pintype "passive"))
    )
    (net (code "61") (name "VOUT") (class "Default")
      (node (ref "APOGEE") (pin "2") (pinfunction "2_2") (pintype "passive"))
      (node (ref "C24") (pin "A") (pinfunction "+_A") (pintype "passive"))
      (node (ref "C34") (pin "1") (pinfunction "1_1") (pintype "passive"))
      (node (ref "MAIN") (pin "1") (pinfunction "1_1") (pintype "passive"))
      (node (ref "R12") (pin "2") (pinfunction "2_2") (pintype "passive"))
      (node (ref "U1") (pin "2") (pinfunction "VOUT_2") (pintype "output"))
    )
    (net (code "62") (name "V_BCKP") (class "Default")
      (node (ref "B2") (pin "+") (pinfunction "+_+") (pintype "power_in"))
      (node (ref "C25") (pin "+") (pinfunction "+_+") (pintype "passive"))
      (node (ref "C27") (pin "2") (pinfunction "2_2") (pintype "passive"))
      (node (ref "R16") (pin "1") (pinfunction "1_1") (pintype "passive"))
      (node (ref "U4") (pin "5") (pinfunction "V_BCKP_5") (pintype "power_in"))
    )
    (net (code "63") (name "XANT") (class "Default")
      (node (ref "C31") (pin "2") (pinfunction "2_2") (pintype "passive"))
      (node (ref "R5") (pin "1") (pinfunction "1_1") (pintype "passive"))
      (node (ref "U4") (pin "11") (pinfunction "EX_ANT_11") (pintype "input"))
    )
    (net (code "64") (name "unconnected-(U3-AUX_CL-Pad7)") (class "Default")
      (node (ref "U3") (pin "7") (pinfunction "AUX_CL_7") (pintype "input"))
    )
    (net (code "65") (name "unconnected-(U3-AUX_DA-Pad6)") (class "Default")
      (node (ref "U3") (pin "6") (pinfunction "AUX_DA_6") (pintype "bidirectional"))
    )
    (net (code "66") (name "unconnected-(U3-RESV-Pad19)") (class "Default")
      (node (ref "U3") (pin "19") (pinfunction "RESV_19") (pintype "passive"))
    )
    (net (code "67") (name "unconnected-(U3-RESV-Pad21)") (class "Default")
      (node (ref "U3") (pin "21") (pinfunction "RESV_21") (pintype "passive"))
    )
    (net (code "68") (name "unconnected-(U5-Pad3V3)") (class "Default")
      (node (ref "U5") (pin "3V3") (pinfunction "3V3_3V3") (pintype "bidirectional"))
    )
    (net (code "69") (name "unconnected-(U5-PadPB0)") (class "Default")
      (node (ref "U5") (pin "PB0") (pinfunction "PB0_PB0") (pintype "bidirectional"))
    )
    (net (code "70") (name "unconnected-(U5-PadPB1)") (class "Default")
      (node (ref "U5") (pin "PB1") (pinfunction "PB1_PB1") (pintype "bidirectional"))
    )
    (net (code "71") (name "unconnected-(U5-PadPB3)") (class "Default")
      (node (ref "U5") (pin "PB3") (pinfunction "PB3_PB3") (pintype "bidirectional"))
    )
    (net (code "72") (name "unconnected-(U5-PadRST)") (class "Default")
      (node (ref "U5") (pin "RST") (pinfunction "RST_RST") (pintype "bidirectional"))
    )
    (net (code "73") (name "unconnected-(U5-PadSWIM)") (class "Default")
      (node (ref "U5") (pin "SWIM") (pinfunction "SWIM_SWIM") (pintype "bidirectional"))
    )
    (net (code "74") (name "unconnected-(U8A-PA5-Pad15)") (class "Default")
      (node (ref "U8") (pin "15") (pinfunction "PA5_15") (pintype "bidirectional"))
    )
    (net (code "75") (name "unconnected-(U8A-PA6-Pad16)") (class "Default")
      (node (ref "U8") (pin "16") (pinfunction "PA6_16") (pintype "bidirectional"))
    )
    (net (code "76") (name "unconnected-(U8A-PA7-Pad17)") (class "Default")
      (node (ref "U8") (pin "17") (pinfunction "PA7_17") (pintype "bidirectional"))
    )
    (net (code "77") (name "unconnected-(U8A-PA8-Pad29)") (class "Default")
      (node (ref "U8") (pin "29") (pinfunction "PA8_29") (pintype "bidirectional"))
    )
    (net (code "78") (name "unconnected-(U8A-PA11-Pad32)") (class "Default")
      (node (ref "U8") (pin "32") (pinfunction "PA11_32") (pintype "bidirectional"))
    )
    (net (code "79") (name "unconnected-(U8A-PB2-Pad20)") (class "Default")
      (node (ref "U8") (pin "20") (pinfunction "PB2_20") (pintype "bidirectional"))
    )
    (net (code "80") (name "unconnected-(U8A-PB4-Pad40)") (class "Default")
      (node (ref "U8") (pin "40") (pinfunction "PB4_40") (pintype "bidirectional"))
    )
    (net (code "81") (name "unconnected-(U8A-PB5-Pad41)") (class "Default")
      (node (ref "U8") (pin "41") (pinfunction "PB5_41") (pintype "bidirectional"))
    )
    (net (code "82") (name "unconnected-(U8A-PB8-Pad45)") (class "Default")
      (node (ref "U8") (pin "45") (pinfunction "PB8_45") (pintype "bidirectional"))
    )
    (net (code "83") (name "unconnected-(U8A-PB9-Pad46)") (class "Default")
      (node (ref "U8") (pin "46") (pinfunction "PB9_46") (pintype "bidirectional"))
    )
    (net (code "84") (name "unconnected-(U8A-PB13-Pad26)") (class "Default")
      (node (ref "U8") (pin "26") (pinfunction "PB13_26") (pintype "bidirectional"))
    )
    (net (code "85") (name "unconnected-(U8A-PB14-Pad27)") (class "Default")
      (node (ref "U8") (pin "27") (pinfunction "PB14_27") (pintype "bidirectional"))
    )
    (net (code "86") (name "unconnected-(U8A-PB15-Pad28)") (class "Default")
      (node (ref "U8") (pin "28") (pinfunction "PB15_28") (pintype "bidirectional"))
    )
    (net (code "87") (name "unconnected-(U8A-PC14-OSC32_IN-Pad3)") (class "Default")
      (node (ref "U8") (pin "3") (pinfunction "PC14-OSC32_IN_3") (pintype "bidirectional"))
    )
    (net (code "88") (name "unconnected-(U8A-PC15-OSC32_OUT-Pad4)") (class "Default")
      (node (ref "U8") (pin "4") (pinfunction "PC15-OSC32_OUT_4") (pintype "bidirectional"))
    )
  )
)
